# Connectors.net
KiCad netlist of a schematic drawn in Altium Designer
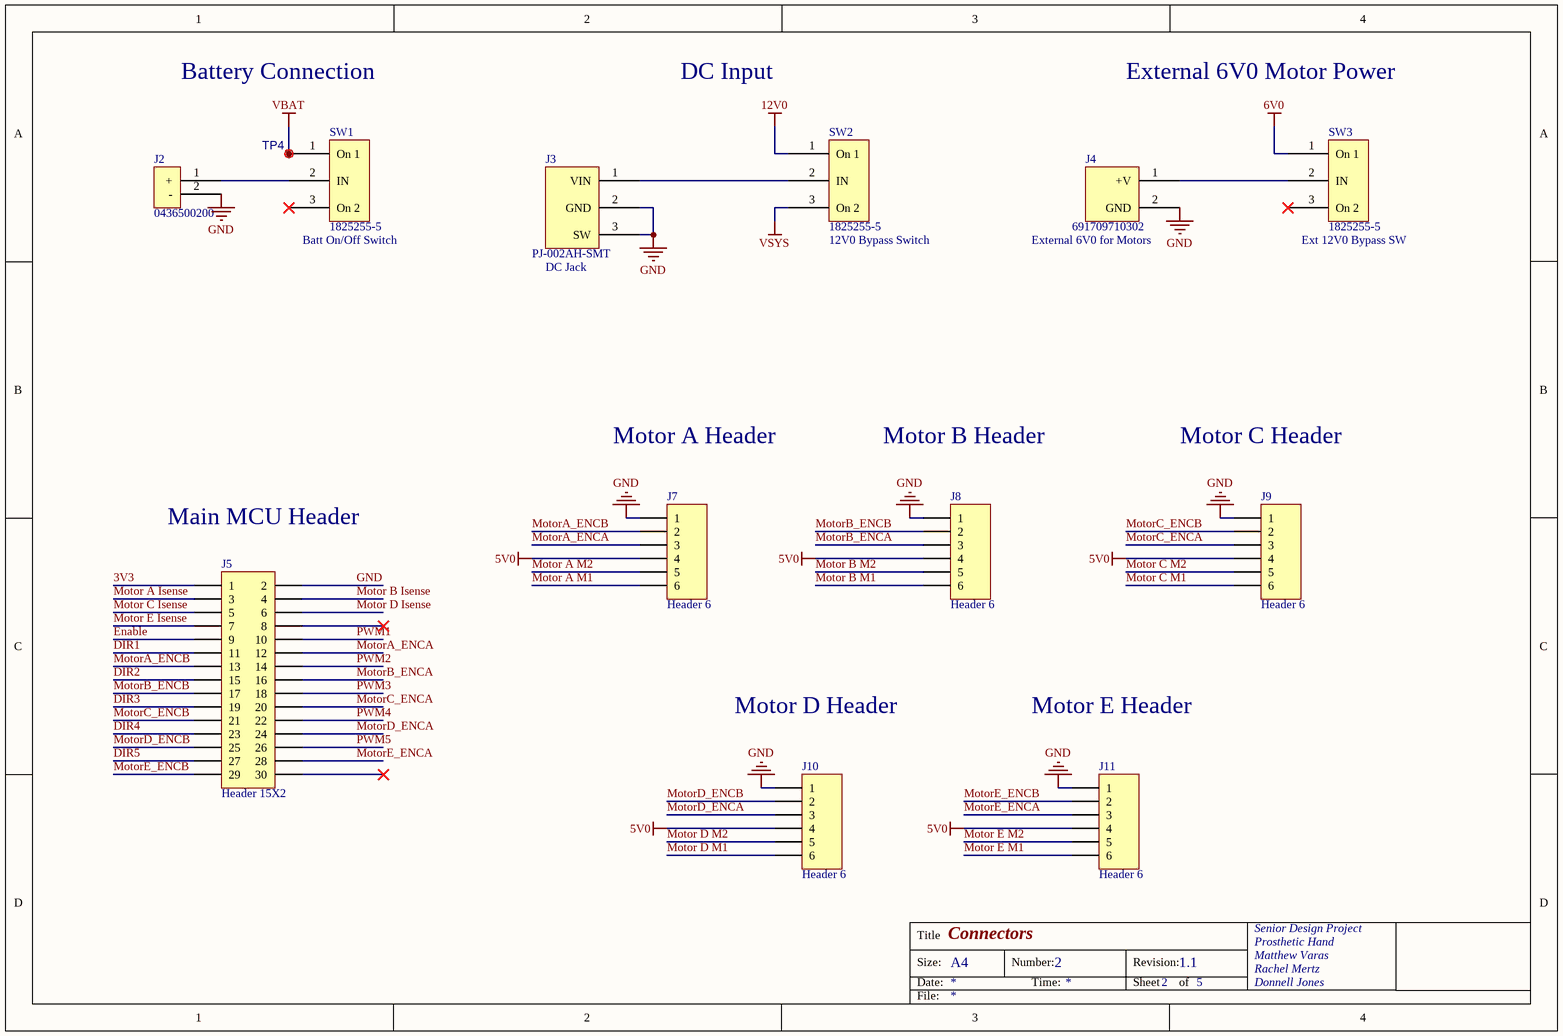
[diagram p0: Connectors.SchDoc]

(export (version "E")
  (design (tool "Eeschema 10.0.6"))
  (components
    (comp (ref "J2")
      (value "0436500200")
      (footprint "43650-0200")
      (description "CONN HEADER 2POS 3MM RT ANG TIN")
      (libsource (lib "Prosthetic Hand Schematic Lib") (part "Battery Connector"))
    )
    (comp (ref "J3")
      (value "PJ-002AH-SMT")
      (footprint "PJ-002AH-SMT")
      (description "CONN POWER JACK 2.1X5.5MM HI CUR")
      (fields (field (name "ALTIUM_UNNAMED_1") "DC Jack"))
      (libsource (lib "Prosthetic Hand Schematic Lib") (part "PJ-002AH-SMT"))
    )
    (comp (ref "J4")
      (value "691709710302")
      (footprint "2-Pin Screw Terminal")
      (description "CONN TERM BLOCK 2POS 5MM BLACK")
      (fields (field (name "ALTIUM_UNNAMED_1") "External 6V0 for Motors"))
      (libsource (lib "Prosthetic Hand Schematic Lib") (part "Screw Terminal 2-pin"))
    )
    (comp (ref "J5")
      (value "Header 15X2")
      (footprint "HDR2X15")
      (description "30 Position Receptacle Connector 0.100\" (2.54mm) Through Hole Tin")
      (fields (field (name "PUBLISHER") "Altium Limited"))
      (libsource (lib "Miscellaneous Connectors") (part "Header 15X2"))
    )
    (comp (ref "J7")
      (value "Header 6")
      (footprint "HDR1X6")
      (description "CONN HEADER VERT 6POS .100 TIN")
      (fields (field (name "PUBLISHER") "Altium Limited"))
      (libsource (lib "Miscellaneous Connectors") (part "Header 6"))
    )
    (comp (ref "J8")
      (value "Header 6")
      (footprint "HDR1X6")
      (description "CONN HEADER VERT 6POS .100 TIN")
      (fields (field (name "PUBLISHER") "Altium Limited"))
      (libsource (lib "Miscellaneous Connectors") (part "Header 6"))
    )
    (comp (ref "J9")
      (value "Header 6")
      (footprint "HDR1X6")
      (description "CONN HEADER VERT 6POS .100 TIN")
      (fields (field (name "PUBLISHER") "Altium Limited"))
      (libsource (lib "Miscellaneous Connectors") (part "Header 6"))
    )
    (comp (ref "J10")
      (value "Header 6")
      (footprint "HDR1X6")
      (description "CONN HEADER VERT 6POS .100 TIN")
      (fields (field (name "PUBLISHER") "Altium Limited"))
      (libsource (lib "Miscellaneous Connectors") (part "Header 6"))
    )
    (comp (ref "J11")
      (value "Header 6")
      (footprint "HDR1X6")
      (description "CONN HEADER VERT 6POS .100 TIN")
      (fields (field (name "PUBLISHER") "Altium Limited"))
      (libsource (lib "Miscellaneous Connectors") (part "Header 6"))
    )
    (comp (ref "SW1")
      (value "1825255-5")
      (footprint "On/Off/On Slider Switch")
      (description "SWITCH SLIDE SPDT 300MA 125V")
      (fields (field (name "ALTIUM_UNNAMED_1") "Batt On/Off Switch"))
      (libsource (lib "Prosthetic Hand Schematic Lib") (part "1825255-5"))
    )
    (comp (ref "SW2")
      (value "1825255-5")
      (footprint "On/Off/On Slider Switch")
      (description "SWITCH SLIDE SPDT 300MA 125V")
      (fields (field (name "ALTIUM_UNNAMED_1") "12V0 Bypass Switch"))
      (libsource (lib "Prosthetic Hand Schematic Lib") (part "1825255-5"))
    )
    (comp (ref "SW3")
      (value "1825255-5")
      (footprint "On/Off/On Slider Switch")
      (description "SWITCH SLIDE SPDT 300MA 125V")
      (fields (field (name "ALTIUM_UNNAMED_1") "Ext 12V0 Bypass SW"))
      (libsource (lib "Prosthetic Hand Schematic Lib") (part "1825255-5"))
    )
    (comp (ref "TP4")
      (value "Test Point")
      (footprint "Testpoint_70")
      (description "Test Pad")
      (libsource (lib "Prosthetic Hand Schematic Lib") (part "Test Point"))
    )
  )
  (nets
    (net (code "1") (name "/3V3") (class "Default")
      (node (ref "J5") (pin "1") (pinfunction "1_1") (pintype "passive"))
    )
    (net (code "2") (name "/DIR1") (class "Default")
      (node (ref "J5") (pin "11") (pinfunction "11_11") (pintype "passive"))
    )
    (net (code "3") (name "/DIR2") (class "Default")
      (node (ref "J5") (pin "15") (pinfunction "15_15") (pintype "passive"))
    )
    (net (code "4") (name "/DIR3") (class "Default")
      (node (ref "J5") (pin "19") (pinfunction "19_19") (pintype "passive"))
    )
    (net (code "5") (name "/DIR4") (class "Default")
      (node (ref "J5") (pin "23") (pinfunction "23_23") (pintype "passive"))
    )
    (net (code "6") (name "/DIR5") (class "Default")
      (node (ref "J5") (pin "27") (pinfunction "27_27") (pintype "passive"))
    )
    (net (code "7") (name "/Enable") (class "Default")
      (node (ref "J5") (pin "9") (pinfunction "9_9") (pintype "passive"))
    )
    (net (code "8") (name "/Motor A Isense") (class "Default")
      (node (ref "J5") (pin "3") (pinfunction "3_3") (pintype "passive"))
    )
    (net (code "9") (name "/Motor A M1") (class "Default")
      (node (ref "J7") (pin "6") (pinfunction "6_6") (pintype "passive"))
    )
    (net (code "10") (name "/Motor A M2") (class "Default")
      (node (ref "J7") (pin "5") (pinfunction "5_5") (pintype "passive"))
    )
    (net (code "11") (name "/Motor B Isense") (class "Default")
      (node (ref "J5") (pin "4") (pinfunction "4_4") (pintype "passive"))
    )
    (net (code "12") (name "/Motor B M1") (class "Default")
      (node (ref "J8") (pin "6") (pinfunction "6_6") (pintype "passive"))
    )
    (net (code "13") (name "/Motor B M2") (class "Default")
      (node (ref "J8") (pin "5") (pinfunction "5_5") (pintype "passive"))
    )
    (net (code "14") (name "/Motor C Isense") (class "Default")
      (node (ref "J5") (pin "5") (pinfunction "5_5") (pintype "passive"))
    )
    (net (code "15") (name "/Motor C M1") (class "Default")
      (node (ref "J9") (pin "6") (pinfunction "6_6") (pintype "passive"))
    )
    (net (code "16") (name "/Motor C M2") (class "Default")
      (node (ref "J9") (pin "5") (pinfunction "5_5") (pintype "passive"))
    )
    (net (code "17") (name "/Motor D Isense") (class "Default")
      (node (ref "J5") (pin "6") (pinfunction "6_6") (pintype "passive"))
    )
    (net (code "18") (name "/Motor D M1") (class "Default")
      (node (ref "J10") (pin "6") (pinfunction "6_6") (pintype "passive"))
    )
    (net (code "19") (name "/Motor D M2") (class "Default")
      (node (ref "J10") (pin "5") (pinfunction "5_5") (pintype "passive"))
    )
    (net (code "20") (name "/Motor E Isense") (class "Default")
      (node (ref "J5") (pin "7") (pinfunction "7_7") (pintype "passive"))
    )
    (net (code "21") (name "/Motor E M1") (class "Default")
      (node (ref "J11") (pin "6") (pinfunction "6_6") (pintype "passive"))
    )
    (net (code "22") (name "/Motor E M2") (class "Default")
      (node (ref "J11") (pin "5") (pinfunction "5_5") (pintype "passive"))
    )
    (net (code "23") (name "/MotorA_ENCA") (class "Default")
      (node (ref "J5") (pin "12") (pinfunction "12_12") (pintype "passive"))
      (node (ref "J7") (pin "3") (pinfunction "3_3") (pintype "passive"))
    )
    (net (code "24") (name "/MotorA_ENCB") (class "Default")
      (node (ref "J5") (pin "13") (pinfunction "13_13") (pintype "passive"))
      (node (ref "J7") (pin "2") (pinfunction "2_2") (pintype "passive"))
    )
    (net (code "25") (name "/MotorB_ENCA") (class "Default")
      (node (ref "J5") (pin "16") (pinfunction "16_16") (pintype "passive"))
      (node (ref "J8") (pin "3") (pinfunction "3_3") (pintype "passive"))
    )
    (net (code "26") (name "/MotorB_ENCB") (class "Default")
      (node (ref "J5") (pin "17") (pinfunction "17_17") (pintype "passive"))
      (node (ref "J8") (pin "2") (pinfunction "2_2") (pintype "passive"))
    )
    (net (code "27") (name "/MotorC_ENCA") (class "Default")
      (node (ref "J5") (pin "20") (pinfunction "20_20") (pintype "passive"))
      (node (ref "J9") (pin "3") (pinfunction "3_3") (pintype "passive"))
    )
    (net (code "28") (name "/MotorC_ENCB") (class "Default")
      (node (ref "J5") (pin "21") (pinfunction "21_21") (pintype "passive"))
      (node (ref "J9") (pin "2") (pinfunction "2_2") (pintype "passive"))
    )
    (net (code "29") (name "/MotorD_ENCA") (class "Default")
      (node (ref "J10") (pin "3") (pinfunction "3_3") (pintype "passive"))
      (node (ref "J5") (pin "24") (pinfunction "24_24") (pintype "passive"))
    )
    (net (code "30") (name "/MotorD_ENCB") (class "Default")
      (node (ref "J10") (pin "2") (pinfunction "2_2") (pintype "passive"))
      (node (ref "J5") (pin "25") (pinfunction "25_25") (pintype "passive"))
    )
    (net (code "31") (name "/MotorE_ENCA") (class "Default")
      (node (ref "J11") (pin "3") (pinfunction "3_3") (pintype "passive"))
      (node (ref "J5") (pin "28") (pinfunction "28_28") (pintype "passive"))
    )
    (net (code "32") (name "/MotorE_ENCB") (class "Default")
      (node (ref "J11") (pin "2") (pinfunction "2_2") (pintype "passive"))
      (node (ref "J5") (pin "29") (pinfunction "29_29") (pintype "passive"))
    )
    (net (code "33") (name "/PWM1") (class "Default")
      (node (ref "J5") (pin "10") (pinfunction "10_10") (pintype "passive"))
    )
    (net (code "34") (name "/PWM2") (class "Default")
      (node (ref "J5") (pin "14") (pinfunction "14_14") (pintype "passive"))
    )
    (net (code "35") (name "/PWM3") (class "Default")
      (node (ref "J5") (pin "18") (pinfunction "18_18") (pintype "passive"))
    )
    (net (code "36") (name "/PWM4") (class "Default")
      (node (ref "J5") (pin "22") (pinfunction "22_22") (pintype "passive"))
    )
    (net (code "37") (name "/PWM5") (class "Default")
      (node (ref "J5") (pin "26") (pinfunction "26_26") (pintype "passive"))
    )
    (net (code "38") (name "5V0") (class "Default")
      (node (ref "J10") (pin "4") (pinfunction "4_4") (pintype "passive"))
      (node (ref "J11") (pin "4") (pinfunction "4_4") (pintype "passive"))
      (node (ref "J7") (pin "4") (pinfunction "4_4") (pintype "passive"))
      (node (ref "J8") (pin "4") (pinfunction "4_4") (pintype "passive"))
      (node (ref "J9") (pin "4") (pinfunction "4_4") (pintype "passive"))
    )
    (net (code "39") (name "6V0") (class "Default")
      (node (ref "SW3") (pin "1") (pinfunction "On_1_1") (pintype "passive"))
    )
    (net (code "40") (name "12V0") (class "Default")
      (node (ref "SW2") (pin "1") (pinfunction "On_1_1") (pintype "passive"))
    )
    (net (code "41") (name "GND") (class "Default")
      (node (ref "J10") (pin "1") (pinfunction "1_1") (pintype "passive"))
      (node (ref "J11") (pin "1") (pinfunction "1_1") (pintype "passive"))
      (node (ref "J2") (pin "2") (pinfunction "-_2") (pintype "passive"))
      (node (ref "J3") (pin "2") (pinfunction "GND_2") (pintype "passive"))
      (node (ref "J3") (pin "3") (pinfunction "SW_3") (pintype "passive"))
      (node (ref "J4") (pin "2") (pinfunction "GND_2") (pintype "passive"))
      (node (ref "J5") (pin "2") (pinfunction "2_2") (pintype "passive"))
      (node (ref "J7") (pin "1") (pinfunction "1_1") (pintype "passive"))
      (node (ref "J8") (pin "1") (pinfunction "1_1") (pintype "passive"))
      (node (ref "J9") (pin "1") (pinfunction "1_1") (pintype "passive"))
    )
    (net (code "42") (name "Net-(J2-+)") (class "Default")
      (node (ref "J2") (pin "1") (pinfunction "+_1") (pintype "passive"))
      (node (ref "SW1") (pin "2") (pinfunction "IN_2") (pintype "passive"))
    )
    (net (code "43") (name "Net-(J3-VIN)") (class "Default")
      (node (ref "J3") (pin "1") (pinfunction "VIN_1") (pintype "passive"))
      (node (ref "SW2") (pin "2") (pinfunction "IN_2") (pintype "passive"))
    )
    (net (code "44") (name "Net-(J4-+V)") (class "Default")
      (node (ref "J4") (pin "1") (pinfunction "+V_1") (pintype "passive"))
      (node (ref "SW3") (pin "2") (pinfunction "IN_2") (pintype "passive"))
    )
    (net (code "45") (name "VBAT") (class "Default")
      (node (ref "SW1") (pin "1") (pinfunction "On_1_1") (pintype "passive"))
      (node (ref "TP4") (pin "1") (pinfunction "M80_1") (pintype "passive"))
    )
    (net (code "46") (name "VSYS") (class "Default")
      (node (ref "SW2") (pin "3") (pinfunction "On_2_3") (pintype "passive"))
    )
    (net (code "47") (name "unconnected-(J5-Pad8)") (class "Default")
      (node (ref "J5") (pin "8") (pinfunction "8_8") (pintype "passive+no_connect"))
    )
    (net (code "48") (name "unconnected-(J5-Pad30)") (class "Default")
      (node (ref "J5") (pin "30") (pinfunction "30_30") (pintype "passive+no_connect"))
    )
    (net (code "49") (name "unconnected-(SW1-On_2-Pad3)") (class "Default")
      (node (ref "SW1") (pin "3") (pinfunction "On_2_3") (pintype "passive+no_connect"))
    )
    (net (code "50") (name "unconnected-(SW3-On_2-Pad3)") (class "Default")
      (node (ref "SW3") (pin "3") (pinfunction "On_2_3") (pintype "passive+no_connect"))
    )
  )
)
